# main.net
KiCad netlist of a schematic drawn in EAGLE
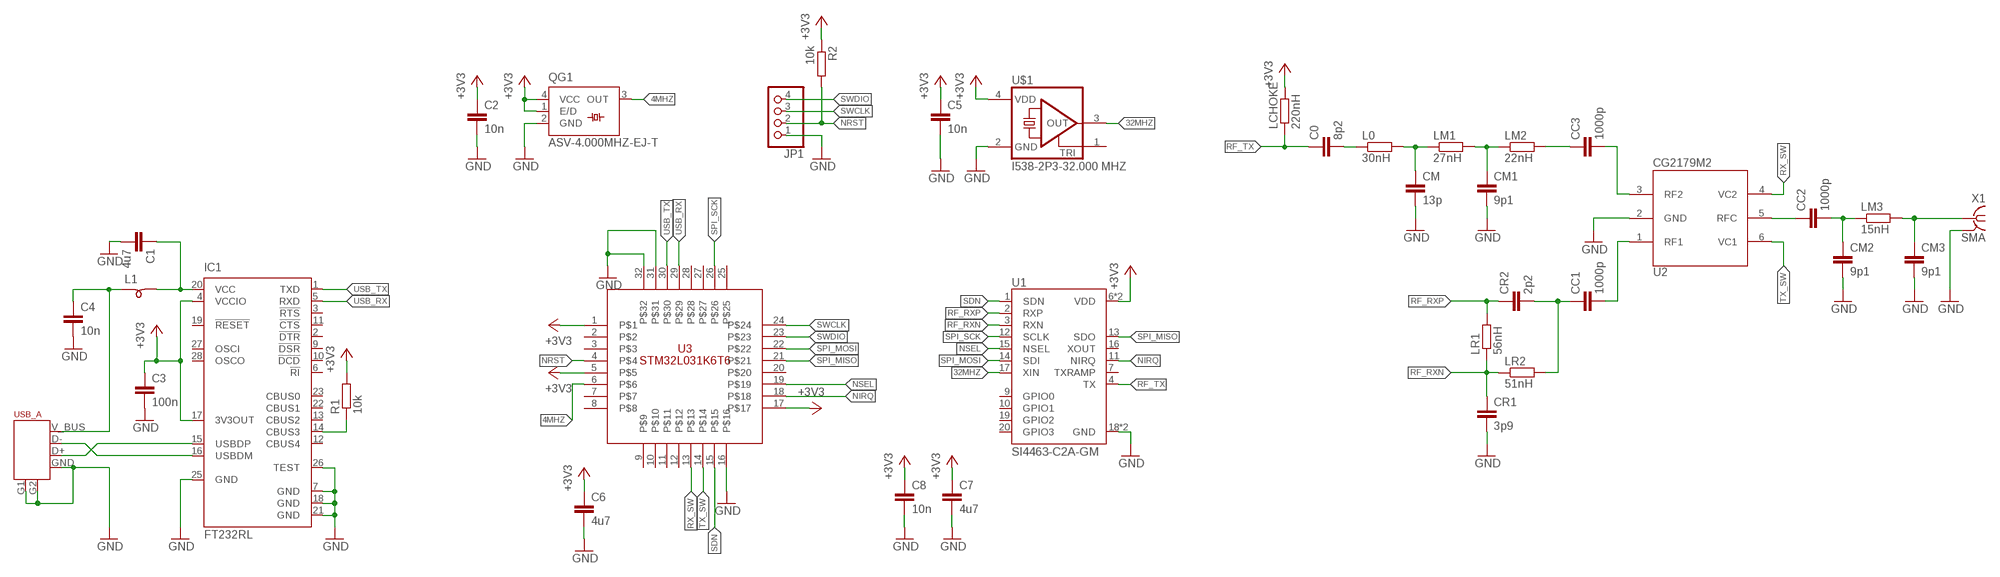
[diagram p0: schematic, sheet 1]

(export (version "E")
  (design (tool "Eeschema 10.0.6"))
  (components
    (comp (ref "C0")
      (value "8p2")
      (footprint "eagle-import:C0805")
      (libsource (lib "eagle-import") (part "C-EUC0805"))
    )
    (comp (ref "C1")
      (value "4u7")
      (footprint "eagle-import:C1206")
      (libsource (lib "eagle-import") (part "C-EUC1206"))
    )
    (comp (ref "C2")
      (value "10n")
      (footprint "eagle-import:C0805")
      (libsource (lib "eagle-import") (part "C-EUC0805"))
    )
    (comp (ref "C3")
      (value "100n")
      (footprint "eagle-import:C0805")
      (libsource (lib "eagle-import") (part "C-EUC0805"))
    )
    (comp (ref "C4")
      (value "10n")
      (footprint "eagle-import:C0805")
      (libsource (lib "eagle-import") (part "C-EUC0805"))
    )
    (comp (ref "C5")
      (value "10n")
      (footprint "eagle-import:C0805")
      (libsource (lib "eagle-import") (part "C-EUC0805"))
    )
    (comp (ref "C6")
      (value "4u7")
      (footprint "eagle-import:C1206")
      (libsource (lib "eagle-import") (part "C-EUC1206"))
    )
    (comp (ref "C7")
      (value "4u7")
      (footprint "eagle-import:C1206")
      (libsource (lib "eagle-import") (part "C-EUC1206"))
    )
    (comp (ref "C8")
      (value "10n")
      (footprint "eagle-import:C0805")
      (libsource (lib "eagle-import") (part "C-EUC0805"))
    )
    (comp (ref "CC1")
      (value "1000p")
      (footprint "eagle-import:C0805")
      (libsource (lib "eagle-import") (part "C-EUC0805"))
    )
    (comp (ref "CC2")
      (value "1000p")
      (footprint "eagle-import:C0805")
      (libsource (lib "eagle-import") (part "C-EUC0805"))
    )
    (comp (ref "CC3")
      (value "1000p")
      (footprint "eagle-import:C0805")
      (libsource (lib "eagle-import") (part "C-EUC0805"))
    )
    (comp (ref "CM")
      (value "13p")
      (footprint "eagle-import:C0805")
      (libsource (lib "eagle-import") (part "C-EUC0805"))
    )
    (comp (ref "CM1")
      (value "9p1")
      (footprint "eagle-import:C0805")
      (libsource (lib "eagle-import") (part "C-EUC0805"))
    )
    (comp (ref "CM2")
      (value "9p1")
      (footprint "eagle-import:C0805")
      (libsource (lib "eagle-import") (part "C-EUC0805"))
    )
    (comp (ref "CM3")
      (value "9p1")
      (footprint "eagle-import:C0805")
      (libsource (lib "eagle-import") (part "C-EUC0805"))
    )
    (comp (ref "CR1")
      (value "3p9")
      (footprint "eagle-import:C0805")
      (libsource (lib "eagle-import") (part "C-EUC0805"))
    )
    (comp (ref "CR2")
      (value "2p2")
      (footprint "eagle-import:C0805")
      (libsource (lib "eagle-import") (part "C-EUC0805"))
    )
    (comp (ref "IC1")
      (value "FT232RL")
      (footprint "eagle-import:SSOP28")
      (libsource (lib "eagle-import") (part "FT232RL"))
    )
    (comp (ref "JP1")
      (value "PINHD-1X4")
      (footprint "eagle-import:1X04")
      (libsource (lib "eagle-import") (part "PINHD-1X4"))
    )
    (comp (ref "L0")
      (value "30nH")
      (footprint "eagle-import:R0805")
      (libsource (lib "eagle-import") (part "R-EU_R0805"))
    )
    (comp (ref "L1")
      (value "SM-B5")
      (footprint "eagle-import:SM-B5")
      (libsource (lib "eagle-import") (part "SM-B5"))
    )
    (comp (ref "LCHOKE")
      (value "220nH")
      (footprint "eagle-import:R0805")
      (libsource (lib "eagle-import") (part "R-EU_R0805"))
    )
    (comp (ref "LM1")
      (value "27nH")
      (footprint "eagle-import:R0805")
      (libsource (lib "eagle-import") (part "R-EU_R0805"))
    )
    (comp (ref "LM2")
      (value "22nH")
      (footprint "eagle-import:R0805")
      (libsource (lib "eagle-import") (part "R-EU_R0805"))
    )
    (comp (ref "LM3")
      (value "15nH")
      (footprint "eagle-import:R0805")
      (libsource (lib "eagle-import") (part "R-EU_R0805"))
    )
    (comp (ref "LR1")
      (value "56nH")
      (footprint "eagle-import:R0805")
      (libsource (lib "eagle-import") (part "R-EU_R0805"))
    )
    (comp (ref "LR2")
      (value "51nH")
      (footprint "eagle-import:R0805")
      (libsource (lib "eagle-import") (part "R-EU_R0805"))
    )
    (comp (ref "QG1")
      (value "ASV-4.000MHZ-EJ-T")
      (footprint "eagle-import:SM77H")
      (libsource (lib "eagle-import") (part "SM77H"))
    )
    (comp (ref "R1")
      (value "10k")
      (footprint "eagle-import:R0805")
      (libsource (lib "eagle-import") (part "R-EU_R0805"))
    )
    (comp (ref "R2")
      (value "10k")
      (footprint "eagle-import:R0805")
      (libsource (lib "eagle-import") (part "R-EU_R0805"))
    )
    (comp (ref "U$1")
      (value "I538-2P3-32.000 MHZ")
      (footprint "eagle-import:ASE")
      (libsource (lib "eagle-import") (part "ASE"))
    )
    (comp (ref "U$2")
      (value "USB_TYPE_A")
      (footprint "eagle-import:USB_A_THT")
      (libsource (lib "eagle-import") (part "USB_TYPE_A"))
    )
    (comp (ref "U1")
      (value "SI4463-C2A-GM")
      (footprint "eagle-import:QFN50P400X400X90-20N")
      (fields (field (name "MF") "Silicon Labs"))
      (libsource (lib "eagle-import") (part "SI4463-C2A-GM"))
    )
    (comp (ref "U2")
      (value "CG2179M2")
      (footprint "eagle-import:SOT363")
      (libsource (lib "eagle-import") (part "CG2179M2"))
    )
    (comp (ref "U3")
      (value "STM32L031K6T6")
      (footprint "eagle-import:LQFP32-7X7")
      (libsource (lib "eagle-import") (part "STM32L011"))
    )
    (comp (ref "X1")
      (value "SMA")
      (footprint "eagle-import:J502-ND-142-0711-821_826")
      (fields (field (name "MF") "JOHNSON COMPONENTS") (field (name "MPN") "142-0711-821"))
      (libsource (lib "eagle-import") (part "SMA-142-0711-821/826"))
    )
  )
  (nets
    (net (code "1") (name "+3V3") (class "Default")
      (node (ref "C2") (pin "1") (pinfunction "1_1") (pintype "passive"))
      (node (ref "C3") (pin "1") (pinfunction "1_1") (pintype "passive"))
      (node (ref "C5") (pin "1") (pinfunction "1_1") (pintype "passive"))
      (node (ref "C6") (pin "1") (pinfunction "1_1") (pintype "passive"))
      (node (ref "C7") (pin "1") (pinfunction "1_1") (pintype "passive"))
      (node (ref "C8") (pin "1") (pinfunction "1_1") (pintype "passive"))
      (node (ref "IC1") (pin "17") (pinfunction "3V3OUT_17") (pintype "output"))
      (node (ref "IC1") (pin "4") (pinfunction "VCCIO_4") (pintype "power_in"))
      (node (ref "LCHOKE") (pin "2") (pinfunction "2_2") (pintype "passive"))
      (node (ref "QG1") (pin "1") (pinfunction "E/D_1") (pintype "input"))
      (node (ref "QG1") (pin "4") (pinfunction "VCC_4") (pintype "power_in"))
      (node (ref "R1") (pin "2") (pinfunction "2_2") (pintype "passive"))
      (node (ref "R2") (pin "1") (pinfunction "1_1") (pintype "passive"))
      (node (ref "U$1") (pin "4") (pinfunction "VDD_4") (pintype "power_in"))
      (node (ref "U1") (pin "6") (pinfunction "VDD_6") (pintype "power_in"))
      (node (ref "U1") (pin "8") (pinfunction "VDD_8") (pintype "power_in"))
      (node (ref "U3") (pin "1") (pinfunction "P$1_1") (pintype "bidirectional"))
      (node (ref "U3") (pin "17") (pinfunction "P$17_17") (pintype "bidirectional"))
      (node (ref "U3") (pin "5") (pinfunction "P$5_5") (pintype "bidirectional"))
    )
    (net (code "2") (name "4MHZ") (class "Default")
      (node (ref "QG1") (pin "3") (pinfunction "OUT_3") (pintype "output"))
      (node (ref "U3") (pin "6") (pinfunction "P$6_6") (pintype "bidirectional"))
    )
    (net (code "3") (name "32MHZ") (class "Default")
      (node (ref "U$1") (pin "3") (pinfunction "OUT_3") (pintype "output"))
      (node (ref "U1") (pin "17") (pinfunction "XIN_17") (pintype "input"))
    )
    (net (code "4") (name "GND") (class "Default")
      (node (ref "C1") (pin "2") (pinfunction "2_2") (pintype "passive"))
      (node (ref "C2") (pin "2") (pinfunction "2_2") (pintype "passive"))
      (node (ref "C3") (pin "2") (pinfunction "2_2") (pintype "passive"))
      (node (ref "C4") (pin "2") (pinfunction "2_2") (pintype "passive"))
      (node (ref "C5") (pin "2") (pinfunction "2_2") (pintype "passive"))
      (node (ref "C6") (pin "2") (pinfunction "2_2") (pintype "passive"))
      (node (ref "C7") (pin "2") (pinfunction "2_2") (pintype "passive"))
      (node (ref "C8") (pin "2") (pinfunction "2_2") (pintype "passive"))
      (node (ref "CM") (pin "2") (pinfunction "2_2") (pintype "passive"))
      (node (ref "CM1") (pin "2") (pinfunction "2_2") (pintype "passive"))
      (node (ref "CM2") (pin "2") (pinfunction "2_2") (pintype "passive"))
      (node (ref "CM3") (pin "2") (pinfunction "2_2") (pintype "passive"))
      (node (ref "CR1") (pin "2") (pinfunction "2_2") (pintype "passive"))
      (node (ref "IC1") (pin "18") (pinfunction "GND_18") (pintype "power_in"))
      (node (ref "IC1") (pin "21") (pinfunction "GND_21") (pintype "power_in"))
      (node (ref "IC1") (pin "25") (pinfunction "GND_25") (pintype "power_in"))
      (node (ref "IC1") (pin "26") (pinfunction "TEST_26") (pintype "input"))
      (node (ref "IC1") (pin "7") (pinfunction "GND_7") (pintype "power_in"))
      (node (ref "JP1") (pin "1") (pinfunction "1_1") (pintype "passive"))
      (node (ref "QG1") (pin "2") (pinfunction "GND_2") (pintype "power_in"))
      (node (ref "U$1") (pin "2") (pinfunction "GND_2") (pintype "power_in"))
      (node (ref "U$2") (pin "G1") (pinfunction "G1_G1") (pintype "bidirectional"))
      (node (ref "U$2") (pin "G2") (pinfunction "G2_G2") (pintype "bidirectional"))
      (node (ref "U$2") (pin "GND") (pinfunction "GND_GND") (pintype "bidirectional"))
      (node (ref "U1") (pin "18") (pinfunction "GND_18") (pintype "power_in"))
      (node (ref "U1") (pin "21") (pinfunction "GND_21") (pintype "power_in"))
      (node (ref "U2") (pin "2") (pinfunction "GND_2") (pintype "bidirectional"))
      (node (ref "U3") (pin "16") (pinfunction "P$16_16") (pintype "bidirectional"))
      (node (ref "U3") (pin "31") (pinfunction "P$31_31") (pintype "bidirectional"))
      (node (ref "U3") (pin "32") (pinfunction "P$32_32") (pintype "bidirectional"))
      (node (ref "X1") (pin "G@1") (pinfunction "2_G@1") (pintype "passive"))
      (node (ref "X1") (pin "G@2") (pinfunction "2_G@2") (pintype "passive"))
      (node (ref "X1") (pin "G@3") (pinfunction "2_G@3") (pintype "passive"))
      (node (ref "X1") (pin "G@4") (pinfunction "2_G@4") (pintype "passive"))
    )
    (net (code "5") (name "NIRQ") (class "Default")
      (node (ref "U1") (pin "11") (pinfunction "NIRQ_11") (pintype "output"))
      (node (ref "U3") (pin "18") (pinfunction "P$18_18") (pintype "bidirectional"))
    )
    (net (code "6") (name "NRST") (class "Default")
      (node (ref "JP1") (pin "2") (pinfunction "2_2") (pintype "passive"))
      (node (ref "R2") (pin "2") (pinfunction "2_2") (pintype "passive"))
      (node (ref "U3") (pin "4") (pinfunction "P$4_4") (pintype "bidirectional"))
    )
    (net (code "7") (name "NSEL") (class "Default")
      (node (ref "U1") (pin "15") (pinfunction "NSEL_15") (pintype "input"))
      (node (ref "U3") (pin "19") (pinfunction "P$19_19") (pintype "bidirectional"))
    )
    (net (code "8") (name "Net-(C0-Pad2)") (class "Default")
      (node (ref "C0") (pin "2") (pinfunction "2_2") (pintype "passive"))
      (node (ref "L0") (pin "1") (pinfunction "1_1") (pintype "passive"))
    )
    (net (code "9") (name "Net-(C4-Pad1)") (class "Default")
      (node (ref "C4") (pin "1") (pinfunction "1_1") (pintype "passive"))
      (node (ref "L1") (pin "1") (pinfunction "1_1") (pintype "passive"))
      (node (ref "U$2") (pin "V_BUS") (pinfunction "V_BUS_V_BUS") (pintype "bidirectional"))
    )
    (net (code "10") (name "Net-(CC1-Pad1)") (class "Default")
      (node (ref "CC1") (pin "1") (pinfunction "1_1") (pintype "passive"))
      (node (ref "CR2") (pin "2") (pinfunction "2_2") (pintype "passive"))
      (node (ref "LR2") (pin "2") (pinfunction "2_2") (pintype "passive"))
    )
    (net (code "11") (name "Net-(CC2-Pad2)") (class "Default")
      (node (ref "CC2") (pin "2") (pinfunction "2_2") (pintype "passive"))
      (node (ref "CM2") (pin "1") (pinfunction "1_1") (pintype "passive"))
      (node (ref "LM3") (pin "1") (pinfunction "1_1") (pintype "passive"))
    )
    (net (code "12") (name "Net-(CC3-Pad1)") (class "Default")
      (node (ref "CC3") (pin "1") (pinfunction "1_1") (pintype "passive"))
      (node (ref "LM2") (pin "2") (pinfunction "2_2") (pintype "passive"))
    )
    (net (code "13") (name "Net-(CM-Pad1)") (class "Default")
      (node (ref "CM") (pin "1") (pinfunction "1_1") (pintype "passive"))
      (node (ref "L0") (pin "2") (pinfunction "2_2") (pintype "passive"))
      (node (ref "LM1") (pin "1") (pinfunction "1_1") (pintype "passive"))
    )
    (net (code "14") (name "Net-(CM1-Pad1)") (class "Default")
      (node (ref "CM1") (pin "1") (pinfunction "1_1") (pintype "passive"))
      (node (ref "LM1") (pin "2") (pinfunction "2_2") (pintype "passive"))
      (node (ref "LM2") (pin "1") (pinfunction "1_1") (pintype "passive"))
    )
    (net (code "15") (name "Net-(CM3-Pad1)") (class "Default")
      (node (ref "CM3") (pin "1") (pinfunction "1_1") (pintype "passive"))
      (node (ref "LM3") (pin "2") (pinfunction "2_2") (pintype "passive"))
      (node (ref "X1") (pin "1") (pinfunction "1_1") (pintype "passive"))
    )
    (net (code "16") (name "Net-(IC1-CBUS3)") (class "Default")
      (node (ref "IC1") (pin "14") (pinfunction "CBUS3_14") (pintype "bidirectional"))
      (node (ref "R1") (pin "1") (pinfunction "1_1") (pintype "passive"))
    )
    (net (code "17") (name "Net-(IC1-USBDM)") (class "Default")
      (node (ref "IC1") (pin "16") (pinfunction "USBDM_16") (pintype "bidirectional"))
      (node (ref "U$2") (pin "D-") (pinfunction "D-_D-") (pintype "bidirectional"))
    )
    (net (code "18") (name "Net-(IC1-USBDP)") (class "Default")
      (node (ref "IC1") (pin "15") (pinfunction "USBDP_15") (pintype "bidirectional"))
      (node (ref "U$2") (pin "D+") (pinfunction "D+_D+") (pintype "bidirectional"))
    )
    (net (code "19") (name "Net-(IC1-VCC)") (class "Default")
      (node (ref "C1") (pin "1") (pinfunction "1_1") (pintype "passive"))
      (node (ref "IC1") (pin "20") (pinfunction "VCC_20") (pintype "power_in"))
      (node (ref "L1") (pin "2") (pinfunction "2_2") (pintype "passive"))
    )
    (net (code "20") (name "Net-(U2-RF1)") (class "Default")
      (node (ref "CC1") (pin "2") (pinfunction "2_2") (pintype "passive"))
      (node (ref "U2") (pin "1") (pinfunction "RF1_1") (pintype "bidirectional"))
    )
    (net (code "21") (name "Net-(U2-RF2)") (class "Default")
      (node (ref "CC3") (pin "2") (pinfunction "2_2") (pintype "passive"))
      (node (ref "U2") (pin "3") (pinfunction "RF2_3") (pintype "bidirectional"))
    )
    (net (code "22") (name "Net-(U2-RFC)") (class "Default")
      (node (ref "CC2") (pin "1") (pinfunction "1_1") (pintype "passive"))
      (node (ref "U2") (pin "5") (pinfunction "RFC_5") (pintype "bidirectional"))
    )
    (net (code "23") (name "RF_RXN") (class "Default")
      (node (ref "CR1") (pin "1") (pinfunction "1_1") (pintype "passive"))
      (node (ref "LR1") (pin "1") (pinfunction "1_1") (pintype "passive"))
      (node (ref "LR2") (pin "1") (pinfunction "1_1") (pintype "passive"))
      (node (ref "U1") (pin "3") (pinfunction "RXN_3") (pintype "input"))
    )
    (net (code "24") (name "RF_RXP") (class "Default")
      (node (ref "CR2") (pin "1") (pinfunction "1_1") (pintype "passive"))
      (node (ref "LR1") (pin "2") (pinfunction "2_2") (pintype "passive"))
      (node (ref "U1") (pin "2") (pinfunction "RXP_2") (pintype "input"))
    )
    (net (code "25") (name "RF_TX") (class "Default")
      (node (ref "C0") (pin "1") (pinfunction "1_1") (pintype "passive"))
      (node (ref "LCHOKE") (pin "1") (pinfunction "1_1") (pintype "passive"))
      (node (ref "U1") (pin "4") (pinfunction "TX_4") (pintype "output"))
    )
    (net (code "26") (name "RX_SW") (class "Default")
      (node (ref "U2") (pin "4") (pinfunction "VC2_4") (pintype "bidirectional"))
      (node (ref "U3") (pin "13") (pinfunction "P$13_13") (pintype "bidirectional"))
    )
    (net (code "27") (name "SDN") (class "Default")
      (node (ref "U1") (pin "1") (pinfunction "SDN_1") (pintype "input"))
      (node (ref "U3") (pin "15") (pinfunction "P$15_15") (pintype "bidirectional"))
    )
    (net (code "28") (name "SPI_MISO") (class "Default")
      (node (ref "U1") (pin "13") (pinfunction "SDO_13") (pintype "output"))
      (node (ref "U3") (pin "21") (pinfunction "P$21_21") (pintype "bidirectional"))
    )
    (net (code "29") (name "SPI_MOSI") (class "Default")
      (node (ref "U1") (pin "14") (pinfunction "SDI_14") (pintype "input"))
      (node (ref "U3") (pin "22") (pinfunction "P$22_22") (pintype "bidirectional"))
    )
    (net (code "30") (name "SPI_SCK") (class "Default")
      (node (ref "U1") (pin "12") (pinfunction "SCLK_12") (pintype "input"))
      (node (ref "U3") (pin "26") (pinfunction "P$26_26") (pintype "bidirectional"))
    )
    (net (code "31") (name "SWCLK") (class "Default")
      (node (ref "JP1") (pin "3") (pinfunction "3_3") (pintype "passive"))
      (node (ref "U3") (pin "24") (pinfunction "P$24_24") (pintype "bidirectional"))
    )
    (net (code "32") (name "SWDIO") (class "Default")
      (node (ref "JP1") (pin "4") (pinfunction "4_4") (pintype "passive"))
      (node (ref "U3") (pin "23") (pinfunction "P$23_23") (pintype "bidirectional"))
    )
    (net (code "33") (name "TX_SW") (class "Default")
      (node (ref "U2") (pin "6") (pinfunction "VC1_6") (pintype "bidirectional"))
      (node (ref "U3") (pin "14") (pinfunction "P$14_14") (pintype "bidirectional"))
    )
    (net (code "34") (name "USB_RX") (class "Default")
      (node (ref "IC1") (pin "5") (pinfunction "RXD_5") (pintype "input"))
      (node (ref "U3") (pin "29") (pinfunction "P$29_29") (pintype "bidirectional"))
    )
    (net (code "35") (name "USB_TX") (class "Default")
      (node (ref "IC1") (pin "1") (pinfunction "TXD_1") (pintype "output"))
      (node (ref "U3") (pin "30") (pinfunction "P$30_30") (pintype "bidirectional"))
    )
    (net (code "36") (name "unconnected-(IC1-CBUS0-Pad23)") (class "Default")
      (node (ref "IC1") (pin "23") (pinfunction "CBUS0_23") (pintype "bidirectional"))
    )
    (net (code "37") (name "unconnected-(IC1-CBUS1-Pad22)") (class "Default")
      (node (ref "IC1") (pin "22") (pinfunction "CBUS1_22") (pintype "bidirectional"))
    )
    (net (code "38") (name "unconnected-(IC1-CBUS2-Pad13)") (class "Default")
      (node (ref "IC1") (pin "13") (pinfunction "CBUS2_13") (pintype "bidirectional"))
    )
    (net (code "39") (name "unconnected-(IC1-CBUS4-Pad12)") (class "Default")
      (node (ref "IC1") (pin "12") (pinfunction "CBUS4_12") (pintype "bidirectional"))
    )
    (net (code "40") (name "unconnected-(IC1-OSCI-Pad27)") (class "Default")
      (node (ref "IC1") (pin "27") (pinfunction "OSCI_27") (pintype "input"))
    )
    (net (code "41") (name "unconnected-(IC1-OSCO-Pad28)") (class "Default")
      (node (ref "IC1") (pin "28") (pinfunction "OSCO_28") (pintype "output"))
    )
    (net (code "42") (name "unconnected-(IC1-~{CTS}-Pad11)") (class "Default")
      (node (ref "IC1") (pin "11") (pinfunction "~{CTS}_11") (pintype "input"))
    )
    (net (code "43") (name "unconnected-(IC1-~{DCD}-Pad10)") (class "Default")
      (node (ref "IC1") (pin "10") (pinfunction "~{DCD}_10") (pintype "input"))
    )
    (net (code "44") (name "unconnected-(IC1-~{DSR}-Pad9)") (class "Default")
      (node (ref "IC1") (pin "9") (pinfunction "~{DSR}_9") (pintype "input"))
    )
    (net (code "45") (name "unconnected-(IC1-~{DTR}-Pad2)") (class "Default")
      (node (ref "IC1") (pin "2") (pinfunction "~{DTR}_2") (pintype "output"))
    )
    (net (code "46") (name "unconnected-(IC1-~{RESET}-Pad19)") (class "Default")
      (node (ref "IC1") (pin "19") (pinfunction "~{RESET}_19") (pintype "input"))
    )
    (net (code "47") (name "unconnected-(IC1-~{RI}-Pad6)") (class "Default")
      (node (ref "IC1") (pin "6") (pinfunction "~{RI}_6") (pintype "input"))
    )
    (net (code "48") (name "unconnected-(IC1-~{RTS}-Pad3)") (class "Default")
      (node (ref "IC1") (pin "3") (pinfunction "~{RTS}_3") (pintype "output"))
    )
    (net (code "49") (name "unconnected-(U$1-TRI-Pad1)") (class "Default")
      (node (ref "U$1") (pin "1") (pinfunction "TRI_1") (pintype "input"))
    )
    (net (code "50") (name "unconnected-(U1-GPIO0-Pad9)") (class "Default")
      (node (ref "U1") (pin "9") (pinfunction "GPIO0_9") (pintype "bidirectional"))
    )
    (net (code "51") (name "unconnected-(U1-GPIO1-Pad10)") (class "Default")
      (node (ref "U1") (pin "10") (pinfunction "GPIO1_10") (pintype "bidirectional"))
    )
    (net (code "52") (name "unconnected-(U1-GPIO2-Pad19)") (class "Default")
      (node (ref "U1") (pin "19") (pinfunction "GPIO2_19") (pintype "bidirectional"))
    )
    (net (code "53") (name "unconnected-(U1-GPIO3-Pad20)") (class "Default")
      (node (ref "U1") (pin "20") (pinfunction "GPIO3_20") (pintype "bidirectional"))
    )
    (net (code "54") (name "unconnected-(U1-TXRAMP-Pad7)") (class "Default")
      (node (ref "U1") (pin "7") (pinfunction "TXRAMP_7") (pintype "output"))
    )
    (net (code "55") (name "unconnected-(U1-XOUT-Pad16)") (class "Default")
      (node (ref "U1") (pin "16") (pinfunction "XOUT_16") (pintype "output"))
    )
    (net (code "56") (name "unconnected-(U3-P$2-Pad2)") (class "Default")
      (node (ref "U3") (pin "2") (pinfunction "P$2_2") (pintype "bidirectional"))
    )
    (net (code "57") (name "unconnected-(U3-P$3-Pad3)") (class "Default")
      (node (ref "U3") (pin "3") (pinfunction "P$3_3") (pintype "bidirectional"))
    )
    (net (code "58") (name "unconnected-(U3-P$7-Pad7)") (class "Default")
      (node (ref "U3") (pin "7") (pinfunction "P$7_7") (pintype "bidirectional"))
    )
    (net (code "59") (name "unconnected-(U3-P$8-Pad8)") (class "Default")
      (node (ref "U3") (pin "8") (pinfunction "P$8_8") (pintype "bidirectional"))
    )
    (net (code "60") (name "unconnected-(U3-P$9-Pad9)") (class "Default")
      (node (ref "U3") (pin "9") (pinfunction "P$9_9") (pintype "bidirectional"))
    )
    (net (code "61") (name "unconnected-(U3-P$10-Pad10)") (class "Default")
      (node (ref "U3") (pin "10") (pinfunction "P$10_10") (pintype "bidirectional"))
    )
    (net (code "62") (name "unconnected-(U3-P$11-Pad11)") (class "Default")
      (node (ref "U3") (pin "11") (pinfunction "P$11_11") (pintype "bidirectional"))
    )
    (net (code "63") (name "unconnected-(U3-P$12-Pad12)") (class "Default")
      (node (ref "U3") (pin "12") (pinfunction "P$12_12") (pintype "bidirectional"))
    )
    (net (code "64") (name "unconnected-(U3-P$20-Pad20)") (class "Default")
      (node (ref "U3") (pin "20") (pinfunction "P$20_20") (pintype "bidirectional"))
    )
    (net (code "65") (name "unconnected-(U3-P$25-Pad25)") (class "Default")
      (node (ref "U3") (pin "25") (pinfunction "P$25_25") (pintype "bidirectional"))
    )
    (net (code "66") (name "unconnected-(U3-P$27-Pad27)") (class "Default")
      (node (ref "U3") (pin "27") (pinfunction "P$27_27") (pintype "bidirectional"))
    )
    (net (code "67") (name "unconnected-(U3-P$28-Pad28)") (class "Default")
      (node (ref "U3") (pin "28") (pinfunction "P$28_28") (pintype "bidirectional"))
    )
  )
)
